# iPod_BoB.net
KiCad netlist of a schematic drawn in EAGLE
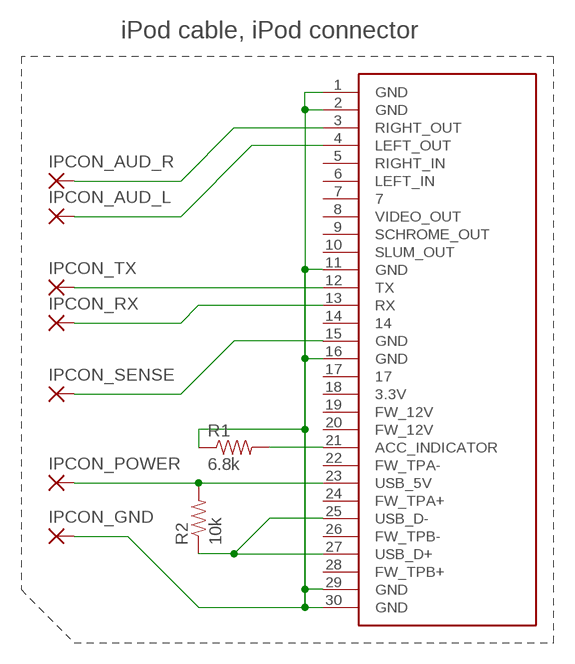
[diagram p0: schematic, sheet 1]

(export (version "E")
  (design (tool "Eeschema 10.0.6"))
  (components
    (comp (ref "IPCON_AUD_L")
      (value "1,6/0,9")
      (footprint "eagle-import:1,6_0,9")
      (libsource (lib "eagle-import") (part "1,6/0,9"))
    )
    (comp (ref "IPCON_AUD_R")
      (value "1,6/0,9")
      (footprint "eagle-import:1,6_0,9")
      (libsource (lib "eagle-import") (part "1,6/0,9"))
    )
    (comp (ref "IPCON_GND")
      (value "1,6/0,9")
      (footprint "eagle-import:1,6_0,9")
      (libsource (lib "eagle-import") (part "1,6/0,9"))
    )
    (comp (ref "IPCON_POWER")
      (value "1,6/0,9")
      (footprint "eagle-import:1,6_0,9")
      (libsource (lib "eagle-import") (part "1,6/0,9"))
    )
    (comp (ref "IPCON_RX")
      (value "1,6/0,9")
      (footprint "eagle-import:1,6_0,9")
      (libsource (lib "eagle-import") (part "1,6/0,9"))
    )
    (comp (ref "IPCON_SENSE")
      (value "1,6/0,9")
      (footprint "eagle-import:1,6_0,9")
      (libsource (lib "eagle-import") (part "1,6/0,9"))
    )
    (comp (ref "IPCON_TX")
      (value "1,6/0,9")
      (footprint "eagle-import:1,6_0,9")
      (libsource (lib "eagle-import") (part "1,6/0,9"))
    )
    (comp (ref "R1")
      (value "6.8k")
      (footprint "eagle-import:0603-RES")
      (libsource (lib "eagle-import") (part "RESISTOR0603-RES"))
    )
    (comp (ref "R2")
      (value "10k")
      (footprint "eagle-import:0603-RES")
      (libsource (lib "eagle-import") (part "RESISTOR0603-RES"))
    )
    (comp (ref "U$1")
      (value "IPOD_CONNECTOR_MALE")
      (footprint "eagle-import:IPOD_MALE_CONNECTOR")
      (libsource (lib "eagle-import") (part "IPOD_CONNECTOR_MALE"))
    )
  )
  (nets
    (net (code "1") (name "Net-(IPCON_AUD_L-P)") (class "Default")
      (node (ref "IPCON_AUD_L") (pin "1") (pinfunction "P_1") (pintype "passive"))
      (node (ref "U$1") (pin "4") (pinfunction "LEFT_OUT_4") (pintype "bidirectional"))
    )
    (net (code "2") (name "Net-(IPCON_AUD_R-P)") (class "Default")
      (node (ref "IPCON_AUD_R") (pin "1") (pinfunction "P_1") (pintype "passive"))
      (node (ref "U$1") (pin "3") (pinfunction "RIGHT_OUT_3") (pintype "bidirectional"))
    )
    (net (code "3") (name "Net-(IPCON_GND-P)") (class "Default")
      (node (ref "IPCON_GND") (pin "1") (pinfunction "P_1") (pintype "passive"))
      (node (ref "R1") (pin "1") (pinfunction "1_1") (pintype "passive"))
      (node (ref "U$1") (pin "1") (pinfunction "GND_1") (pintype "bidirectional"))
      (node (ref "U$1") (pin "11") (pinfunction "GND_11") (pintype "bidirectional"))
      (node (ref "U$1") (pin "16") (pinfunction "GND_16") (pintype "bidirectional"))
      (node (ref "U$1") (pin "2") (pinfunction "GND_2") (pintype "bidirectional"))
      (node (ref "U$1") (pin "29") (pinfunction "GND_29") (pintype "bidirectional"))
      (node (ref "U$1") (pin "30") (pinfunction "GND_30") (pintype "bidirectional"))
    )
    (net (code "4") (name "Net-(IPCON_POWER-P)") (class "Default")
      (node (ref "IPCON_POWER") (pin "1") (pinfunction "P_1") (pintype "passive"))
      (node (ref "R2") (pin "2") (pinfunction "2_2") (pintype "passive"))
      (node (ref "U$1") (pin "23") (pinfunction "USB_5V_23") (pintype "bidirectional"))
    )
    (net (code "5") (name "Net-(IPCON_RX-P)") (class "Default")
      (node (ref "IPCON_RX") (pin "1") (pinfunction "P_1") (pintype "passive"))
      (node (ref "U$1") (pin "13") (pinfunction "RX_13") (pintype "bidirectional"))
    )
    (net (code "6") (name "Net-(IPCON_SENSE-P)") (class "Default")
      (node (ref "IPCON_SENSE") (pin "1") (pinfunction "P_1") (pintype "passive"))
      (node (ref "U$1") (pin "15") (pinfunction "GND_15") (pintype "bidirectional"))
    )
    (net (code "7") (name "Net-(IPCON_TX-P)") (class "Default")
      (node (ref "IPCON_TX") (pin "1") (pinfunction "P_1") (pintype "passive"))
      (node (ref "U$1") (pin "12") (pinfunction "TX_12") (pintype "bidirectional"))
    )
    (net (code "8") (name "Net-(U$1-ACC_INDICATOR)") (class "Default")
      (node (ref "R1") (pin "2") (pinfunction "2_2") (pintype "passive"))
      (node (ref "U$1") (pin "21") (pinfunction "ACC_INDICATOR_21") (pintype "bidirectional"))
    )
    (net (code "9") (name "Net-(U$1-USB_D+)") (class "Default")
      (node (ref "R2") (pin "1") (pinfunction "1_1") (pintype "passive"))
      (node (ref "U$1") (pin "25") (pinfunction "USB_D-_25") (pintype "bidirectional"))
      (node (ref "U$1") (pin "27") (pinfunction "USB_D+_27") (pintype "bidirectional"))
    )
    (net (code "10") (name "unconnected-(U$1-3.3V-Pad18)") (class "Default")
      (node (ref "U$1") (pin "18") (pinfunction "3.3V_18") (pintype "bidirectional"))
    )
    (net (code "11") (name "unconnected-(U$1-FW_12V-Pad19)") (class "Default")
      (node (ref "U$1") (pin "19") (pinfunction "FW_12V_19") (pintype "bidirectional"))
    )
    (net (code "12") (name "unconnected-(U$1-FW_12V-Pad20)") (class "Default")
      (node (ref "U$1") (pin "20") (pinfunction "FW_12V_20") (pintype "bidirectional"))
    )
    (net (code "13") (name "unconnected-(U$1-FW_TPA+-Pad24)") (class "Default")
      (node (ref "U$1") (pin "24") (pinfunction "FW_TPA+_24") (pintype "bidirectional"))
    )
    (net (code "14") (name "unconnected-(U$1-FW_TPA--Pad22)") (class "Default")
      (node (ref "U$1") (pin "22") (pinfunction "FW_TPA-_22") (pintype "bidirectional"))
    )
    (net (code "15") (name "unconnected-(U$1-FW_TPB+-Pad28)") (class "Default")
      (node (ref "U$1") (pin "28") (pinfunction "FW_TPB+_28") (pintype "bidirectional"))
    )
    (net (code "16") (name "unconnected-(U$1-FW_TPB--Pad26)") (class "Default")
      (node (ref "U$1") (pin "26") (pinfunction "FW_TPB-_26") (pintype "bidirectional"))
    )
    (net (code "17") (name "unconnected-(U$1-LEFT_IN-Pad6)") (class "Default")
      (node (ref "U$1") (pin "6") (pinfunction "LEFT_IN_6") (pintype "bidirectional"))
    )
    (net (code "18") (name "unconnected-(U$1-Pad7)") (class "Default")
      (node (ref "U$1") (pin "7") (pinfunction "7_7") (pintype "bidirectional"))
    )
    (net (code "19") (name "unconnected-(U$1-Pad14)") (class "Default")
      (node (ref "U$1") (pin "14") (pinfunction "14_14") (pintype "bidirectional"))
    )
    (net (code "20") (name "unconnected-(U$1-Pad17)") (class "Default")
      (node (ref "U$1") (pin "17") (pinfunction "17_17") (pintype "bidirectional"))
    )
    (net (code "21") (name "unconnected-(U$1-RIGHT_IN-Pad5)") (class "Default")
      (node (ref "U$1") (pin "5") (pinfunction "RIGHT_IN_5") (pintype "bidirectional"))
    )
    (net (code "22") (name "unconnected-(U$1-SCHROME_OUT-Pad9)") (class "Default")
      (node (ref "U$1") (pin "9") (pinfunction "SCHROME_OUT_9") (pintype "bidirectional"))
    )
    (net (code "23") (name "unconnected-(U$1-SLUM_OUT-Pad10)") (class "Default")
      (node (ref "U$1") (pin "10") (pinfunction "SLUM_OUT_10") (pintype "bidirectional"))
    )
    (net (code "24") (name "unconnected-(U$1-VIDEO_OUT-Pad8)") (class "Default")
      (node (ref "U$1") (pin "8") (pinfunction "VIDEO_OUT_8") (pintype "bidirectional"))
    )
  )
)
